# ProPrj_KiwiKey_2025-07-17.net
KiCad netlist of a schematic drawn in EasyEDA Pro
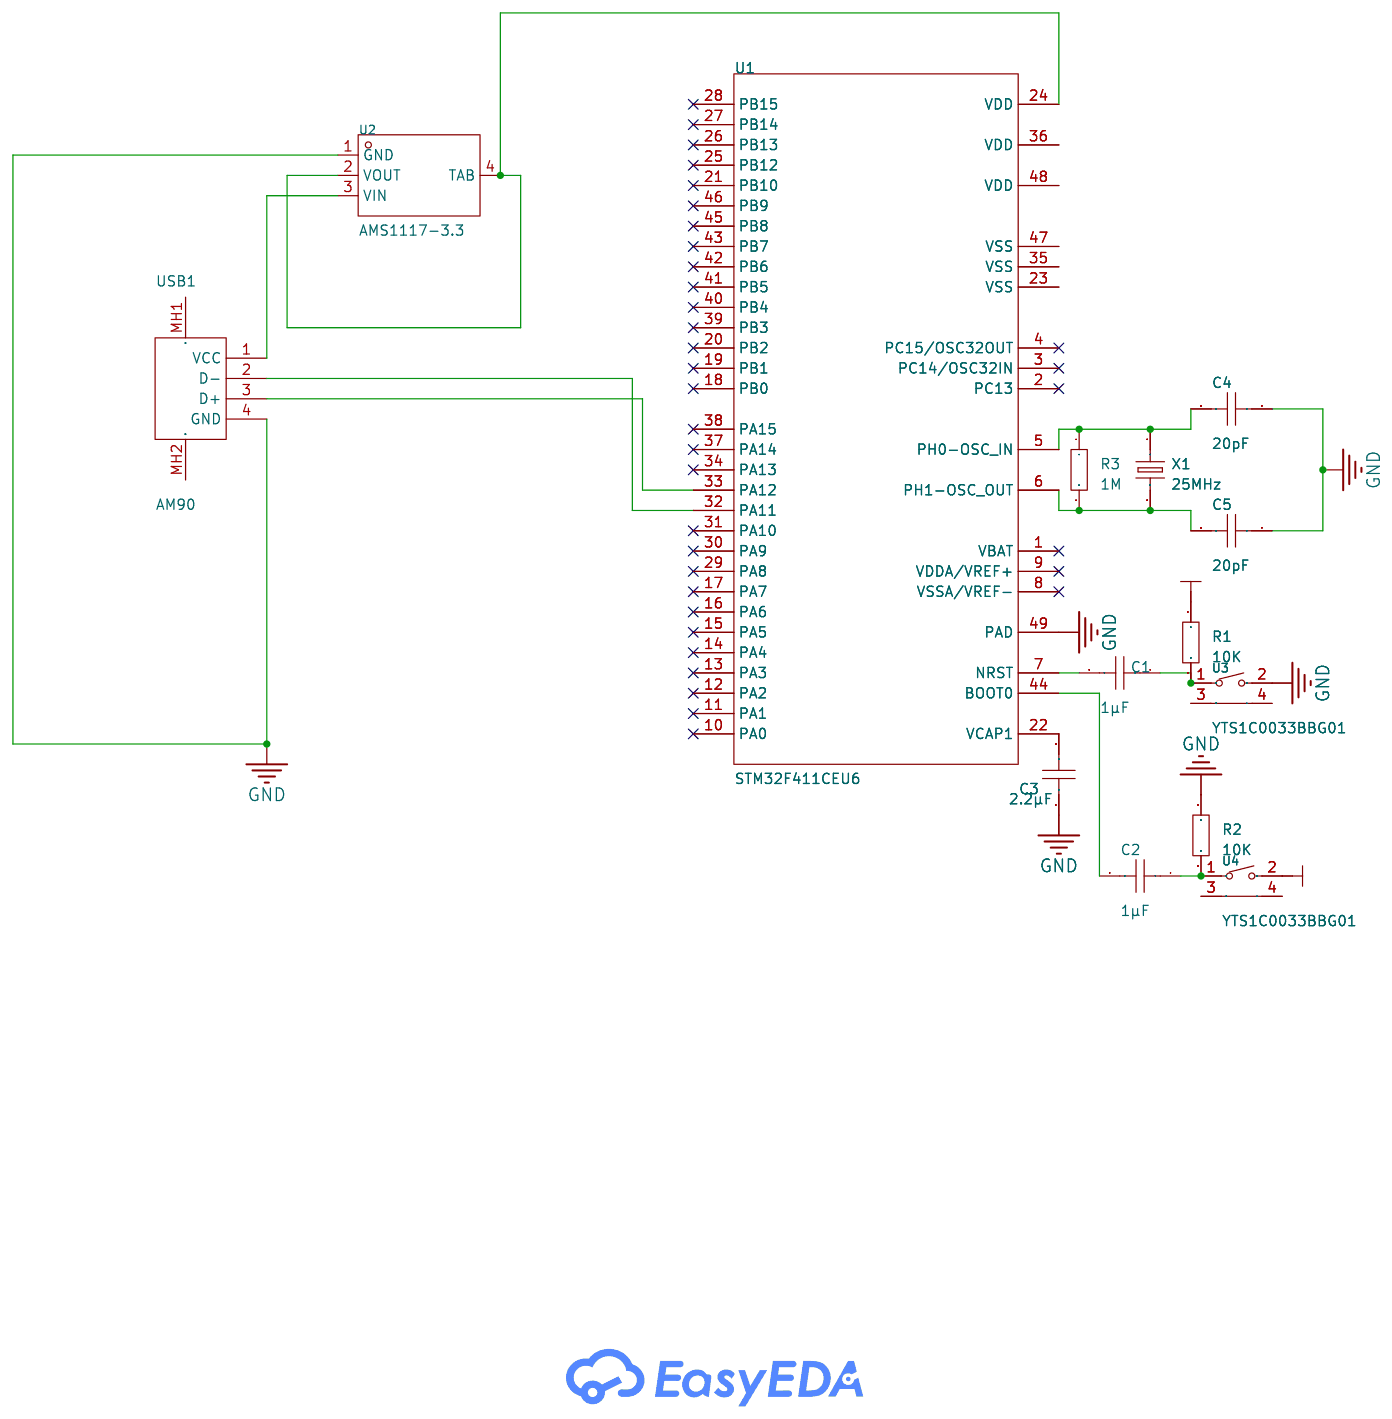
[diagram p0: schematic sheet]

(export (version "E")
  (design (tool "Eeschema 10.0.6"))
  (components
    (comp (ref "C1") (value "1µF") (footprint "easyedapro:C0603") (libsource (lib "easyedapro") (part "CAP")))
    (comp (ref "C2") (value "1µF") (footprint "easyedapro:C0603") (libsource (lib "easyedapro") (part "CAP")))
    (comp (ref "C3")
      (value "2.2µF")
      (footprint "easyedapro:C0603")
      (libsource (lib "easyedapro") (part "CAP"))
    )
    (comp (ref "C4")
      (value "20pF")
      (footprint "easyedapro:C0603")
      (libsource (lib "easyedapro") (part "CAP"))
    )
    (comp (ref "C5")
      (value "20pF")
      (footprint "easyedapro:C0603")
      (libsource (lib "easyedapro") (part "CAP"))
    )
    (comp (ref "R1") (value "10K") (footprint "easyedapro:R0603") (libsource (lib "easyedapro") (part "Res")))
    (comp (ref "R2") (value "10K") (footprint "easyedapro:R0603") (libsource (lib "easyedapro") (part "Res")))
    (comp (ref "R3") (value "1M") (footprint "easyedapro:R0603") (libsource (lib "easyedapro") (part "Res")))
    (comp (ref "U1")
      (value "STM32F411CEU6")
      (footprint "easyedapro:UFQFPN-48_L7.0-W7.0-P0.50-BL-EP")
      (fields (field (name "Manufacturer") "ST(意法半导体)"))
      (libsource (lib "easyedapro") (part "STM32F411CEU6"))
    )
    (comp (ref "U2")
      (value "AMS1117-3.3")
      (footprint "easyedapro:SOT-223-3_L6.5-W3.4-P2.30-LS7.0-BR")
      (fields (field (name "Manufacturer") "PUOLOP(迪浦)"))
      (libsource (lib "easyedapro") (part "AMS1117-3.3_C351784"))
    )
    (comp (ref "U3")
      (value "YTS1C0033BBG01")
      (footprint "easyedapro:SW-SMD_YIYUAN_YTS1C003XXX")
      (fields (field (name "Manufacturer") "YIYUAN(怡远)"))
      (libsource (lib "easyedapro") (part "YTS1C0033BBG01"))
    )
    (comp (ref "U4")
      (value "YTS1C0033BBG01")
      (footprint "easyedapro:SW-SMD_YIYUAN_YTS1C003XXX")
      (fields (field (name "Manufacturer") "YIYUAN(怡远)"))
      (libsource (lib "easyedapro") (part "YTS1C0033BBG01"))
    )
    (comp (ref "USB1")
      (value "AM90")
      (footprint "easyedapro:USB-AM-TH_AM90")
      (fields (field (name "Manufacturer") "SHOU HAN(首韩)"))
      (libsource (lib "easyedapro") (part "AM90"))
    )
    (comp (ref "X1")
      (value "25MHz")
      (footprint "easyedapro:HC-49US_L11.5-W4.5-P4.88")
      (fields
        (field (name "Manufacturer Part") "XIHCELNANF-25MHZ")
        (field (name "Manufacturer") "TAITIEN(泰艺电子)")
      )
      (libsource (lib "easyedapro") (part "XIHCELNANF-25MHZ"))
    )
  )
  (nets
    (net (code "1") (name "3.3V") (class "Default")
      (node (ref "R1") (pin "1") (pinfunction "1_1") (pintype "input"))
      (node (ref "U4") (pin "2") (pinfunction "2_2") (pintype "input"))
    )
    (net (code "2") (name "GND") (class "Default")
      (node (ref "C3") (pin "1") (pinfunction "1_1") (pintype "input"))
      (node (ref "C4") (pin "1") (pinfunction "1_1") (pintype "input"))
      (node (ref "C5") (pin "1") (pinfunction "1_1") (pintype "input"))
      (node (ref "R2") (pin "1") (pinfunction "1_1") (pintype "input"))
      (node (ref "U1") (pin "49") (pinfunction "PAD_49") (pintype "unspecified"))
      (node (ref "U2") (pin "1") (pinfunction "GND_1") (pintype "input"))
      (node (ref "U3") (pin "2") (pinfunction "2_2") (pintype "input"))
      (node (ref "USB1") (pin "4") (pinfunction "GND_4") (pintype "input"))
    )
    (net (code "3") (name "Net-(C1-Pad1)") (class "Default")
      (node (ref "C1") (pin "1") (pinfunction "1_1") (pintype "input"))
      (node (ref "R1") (pin "2") (pinfunction "2_2") (pintype "input"))
      (node (ref "U3") (pin "1") (pinfunction "1_1") (pintype "input"))
    )
    (net (code "4") (name "Net-(C2-Pad1)") (class "Default")
      (node (ref "C2") (pin "1") (pinfunction "1_1") (pintype "input"))
      (node (ref "R2") (pin "2") (pinfunction "2_2") (pintype "input"))
      (node (ref "U4") (pin "1") (pinfunction "1_1") (pintype "input"))
    )
    (net (code "5") (name "Net-(U1-BOOT0)") (class "Default")
      (node (ref "C2") (pin "2") (pinfunction "2_2") (pintype "input"))
      (node (ref "U1") (pin "44") (pinfunction "BOOT0_44") (pintype "input"))
    )
    (net (code "6") (name "Net-(U1-NRST)") (class "Default")
      (node (ref "C1") (pin "2") (pinfunction "2_2") (pintype "input"))
      (node (ref "U1") (pin "7") (pinfunction "NRST_7") (pintype "unspecified"))
    )
    (net (code "7") (name "Net-(U1-PA11)") (class "Default")
      (node (ref "U1") (pin "32") (pinfunction "PA11_32") (pintype "unspecified"))
      (node (ref "USB1") (pin "2") (pinfunction "D-_2") (pintype "input"))
    )
    (net (code "8") (name "Net-(U1-PA12)") (class "Default")
      (node (ref "U1") (pin "33") (pinfunction "PA12_33") (pintype "unspecified"))
      (node (ref "USB1") (pin "3") (pinfunction "D+_3") (pintype "input"))
    )
    (net (code "9") (name "Net-(U1-PH0-OSC_IN)") (class "Default")
      (node (ref "C4") (pin "2") (pinfunction "2_2") (pintype "input"))
      (node (ref "R3") (pin "1") (pinfunction "1_1") (pintype "input"))
      (node (ref "U1") (pin "5") (pinfunction "PH0-OSC_IN_5") (pintype "unspecified"))
      (node (ref "X1") (pin "1") (pinfunction "1_1") (pintype "unspecified"))
    )
    (net (code "10") (name "Net-(U1-PH1-OSC_OUT)") (class "Default")
      (node (ref "C5") (pin "2") (pinfunction "2_2") (pintype "input"))
      (node (ref "R3") (pin "2") (pinfunction "2_2") (pintype "input"))
      (node (ref "U1") (pin "6") (pinfunction "PH1-OSC_OUT_6") (pintype "unspecified"))
      (node (ref "X1") (pin "2") (pinfunction "2_2") (pintype "unspecified"))
    )
    (net (code "11") (name "Net-(U1-VCAP1)") (class "Default")
      (node (ref "C3") (pin "2") (pinfunction "2_2") (pintype "input"))
      (node (ref "U1") (pin "22") (pinfunction "VCAP1_22") (pintype "unspecified"))
    )
    (net (code "12") (name "Net-(U2-TAB)") (class "Default")
      (node (ref "U1") (pin "24") (pinfunction "VDD_24") (pintype "unspecified"))
      (node (ref "U2") (pin "2") (pinfunction "VOUT_2") (pintype "input"))
      (node (ref "U2") (pin "4") (pinfunction "TAB_4") (pintype "input"))
    )
    (net (code "13") (name "Net-(U2-VIN)") (class "Default")
      (node (ref "U2") (pin "3") (pinfunction "VIN_3") (pintype "input"))
      (node (ref "USB1") (pin "1") (pinfunction "VCC_1") (pintype "input"))
    )
    (net (code "14") (name "unconnected-(U1-PA0-Pad10)") (class "Default")
      (node (ref "U1") (pin "10") (pinfunction "PA0_10") (pintype "unspecified+no_connect"))
    )
    (net (code "15") (name "unconnected-(U1-PA1-Pad11)") (class "Default")
      (node (ref "U1") (pin "11") (pinfunction "PA1_11") (pintype "unspecified+no_connect"))
    )
    (net (code "16") (name "unconnected-(U1-PA2-Pad12)") (class "Default")
      (node (ref "U1") (pin "12") (pinfunction "PA2_12") (pintype "unspecified+no_connect"))
    )
    (net (code "17") (name "unconnected-(U1-PA3-Pad13)") (class "Default")
      (node (ref "U1") (pin "13") (pinfunction "PA3_13") (pintype "unspecified+no_connect"))
    )
    (net (code "18") (name "unconnected-(U1-PA4-Pad14)") (class "Default")
      (node (ref "U1") (pin "14") (pinfunction "PA4_14") (pintype "unspecified+no_connect"))
    )
    (net (code "19") (name "unconnected-(U1-PA5-Pad15)") (class "Default")
      (node (ref "U1") (pin "15") (pinfunction "PA5_15") (pintype "unspecified+no_connect"))
    )
    (net (code "20") (name "unconnected-(U1-PA6-Pad16)") (class "Default")
      (node (ref "U1") (pin "16") (pinfunction "PA6_16") (pintype "unspecified+no_connect"))
    )
    (net (code "21") (name "unconnected-(U1-PA7-Pad17)") (class "Default")
      (node (ref "U1") (pin "17") (pinfunction "PA7_17") (pintype "unspecified+no_connect"))
    )
    (net (code "22") (name "unconnected-(U1-PA8-Pad29)") (class "Default")
      (node (ref "U1") (pin "29") (pinfunction "PA8_29") (pintype "unspecified+no_connect"))
    )
    (net (code "23") (name "unconnected-(U1-PA9-Pad30)") (class "Default")
      (node (ref "U1") (pin "30") (pinfunction "PA9_30") (pintype "unspecified+no_connect"))
    )
    (net (code "24") (name "unconnected-(U1-PA10-Pad31)") (class "Default")
      (node (ref "U1") (pin "31") (pinfunction "PA10_31") (pintype "unspecified+no_connect"))
    )
    (net (code "25") (name "unconnected-(U1-PA13-Pad34)") (class "Default")
      (node (ref "U1") (pin "34") (pinfunction "PA13_34") (pintype "unspecified+no_connect"))
    )
    (net (code "26") (name "unconnected-(U1-PA14-Pad37)") (class "Default")
      (node (ref "U1") (pin "37") (pinfunction "PA14_37") (pintype "unspecified+no_connect"))
    )
    (net (code "27") (name "unconnected-(U1-PA15-Pad38)") (class "Default")
      (node (ref "U1") (pin "38") (pinfunction "PA15_38") (pintype "unspecified+no_connect"))
    )
    (net (code "28") (name "unconnected-(U1-PB0-Pad18)") (class "Default")
      (node (ref "U1") (pin "18") (pinfunction "PB0_18") (pintype "unspecified+no_connect"))
    )
    (net (code "29") (name "unconnected-(U1-PB1-Pad19)") (class "Default")
      (node (ref "U1") (pin "19") (pinfunction "PB1_19") (pintype "unspecified+no_connect"))
    )
    (net (code "30") (name "unconnected-(U1-PB2-Pad20)") (class "Default")
      (node (ref "U1") (pin "20") (pinfunction "PB2_20") (pintype "unspecified+no_connect"))
    )
    (net (code "31") (name "unconnected-(U1-PB3-Pad39)") (class "Default")
      (node (ref "U1") (pin "39") (pinfunction "PB3_39") (pintype "unspecified+no_connect"))
    )
    (net (code "32") (name "unconnected-(U1-PB4-Pad40)") (class "Default")
      (node (ref "U1") (pin "40") (pinfunction "PB4_40") (pintype "unspecified+no_connect"))
    )
    (net (code "33") (name "unconnected-(U1-PB5-Pad41)") (class "Default")
      (node (ref "U1") (pin "41") (pinfunction "PB5_41") (pintype "unspecified+no_connect"))
    )
    (net (code "34") (name "unconnected-(U1-PB6-Pad42)") (class "Default")
      (node (ref "U1") (pin "42") (pinfunction "PB6_42") (pintype "unspecified+no_connect"))
    )
    (net (code "35") (name "unconnected-(U1-PB7-Pad43)") (class "Default")
      (node (ref "U1") (pin "43") (pinfunction "PB7_43") (pintype "unspecified+no_connect"))
    )
    (net (code "36") (name "unconnected-(U1-PB8-Pad45)") (class "Default")
      (node (ref "U1") (pin "45") (pinfunction "PB8_45") (pintype "unspecified+no_connect"))
    )
    (net (code "37") (name "unconnected-(U1-PB9-Pad46)") (class "Default")
      (node (ref "U1") (pin "46") (pinfunction "PB9_46") (pintype "unspecified+no_connect"))
    )
    (net (code "38") (name "unconnected-(U1-PB10-Pad21)") (class "Default")
      (node (ref "U1") (pin "21") (pinfunction "PB10_21") (pintype "unspecified+no_connect"))
    )
    (net (code "39") (name "unconnected-(U1-PB12-Pad25)") (class "Default")
      (node (ref "U1") (pin "25") (pinfunction "PB12_25") (pintype "unspecified+no_connect"))
    )
    (net (code "40") (name "unconnected-(U1-PB13-Pad26)") (class "Default")
      (node (ref "U1") (pin "26") (pinfunction "PB13_26") (pintype "unspecified+no_connect"))
    )
    (net (code "41") (name "unconnected-(U1-PB14-Pad27)") (class "Default")
      (node (ref "U1") (pin "27") (pinfunction "PB14_27") (pintype "unspecified+no_connect"))
    )
    (net (code "42") (name "unconnected-(U1-PB15-Pad28)") (class "Default")
      (node (ref "U1") (pin "28") (pinfunction "PB15_28") (pintype "unspecified+no_connect"))
    )
    (net (code "43") (name "unconnected-(U1-PC13-Pad2)") (class "Default")
      (node (ref "U1") (pin "2") (pinfunction "PC13_2") (pintype "unspecified+no_connect"))
    )
    (net (code "44") (name "unconnected-(U1-PC14{slash}OSC32IN-Pad3)") (class "Default")
      (node (ref "U1") (pin "3") (pinfunction "PC14/OSC32IN_3") (pintype "unspecified+no_connect"))
    )
    (net (code "45") (name "unconnected-(U1-PC15{slash}OSC32OUT-Pad4)") (class "Default")
      (node (ref "U1") (pin "4") (pinfunction "PC15/OSC32OUT_4") (pintype "unspecified+no_connect"))
    )
    (net (code "46") (name "unconnected-(U1-VBAT-Pad1)") (class "Default")
      (node (ref "U1") (pin "1") (pinfunction "VBAT_1") (pintype "unspecified+no_connect"))
    )
    (net (code "47") (name "unconnected-(U1-VDD-Pad36)") (class "Default")
      (node (ref "U1") (pin "36") (pinfunction "VDD_36") (pintype "unspecified"))
    )
    (net (code "48") (name "unconnected-(U1-VDD-Pad48)") (class "Default")
      (node (ref "U1") (pin "48") (pinfunction "VDD_48") (pintype "unspecified"))
    )
    (net (code "49") (name "unconnected-(U1-VDDA{slash}VREF+-Pad9)") (class "Default")
      (node (ref "U1") (pin "9") (pinfunction "VDDA/VREF+_9") (pintype "unspecified+no_connect"))
    )
    (net (code "50") (name "unconnected-(U1-VSS-Pad23)") (class "Default")
      (node (ref "U1") (pin "23") (pinfunction "VSS_23") (pintype "unspecified"))
    )
    (net (code "51") (name "unconnected-(U1-VSS-Pad35)") (class "Default")
      (node (ref "U1") (pin "35") (pinfunction "VSS_35") (pintype "unspecified"))
    )
    (net (code "52") (name "unconnected-(U1-VSS-Pad47)") (class "Default")
      (node (ref "U1") (pin "47") (pinfunction "VSS_47") (pintype "unspecified"))
    )
    (net (code "53") (name "unconnected-(U1-VSSA{slash}VREF--Pad8)") (class "Default")
      (node (ref "U1") (pin "8") (pinfunction "VSSA/VREF-_8") (pintype "unspecified+no_connect"))
    )
    (net (code "54") (name "unconnected-(U3-Pad3)") (class "Default")
      (node (ref "U3") (pin "3") (pinfunction "3_3") (pintype "input"))
    )
    (net (code "55") (name "unconnected-(U3-Pad4)") (class "Default")
      (node (ref "U3") (pin "4") (pinfunction "4_4") (pintype "input"))
    )
    (net (code "56") (name "unconnected-(U4-Pad3)") (class "Default")
      (node (ref "U4") (pin "3") (pinfunction "3_3") (pintype "input"))
    )
    (net (code "57") (name "unconnected-(U4-Pad4)") (class "Default")
      (node (ref "U4") (pin "4") (pinfunction "4_4") (pintype "input"))
    )
    (net (code "58") (name "unconnected-(USB1-PadMH1)") (class "Default")
      (node (ref "USB1") (pin "MH1") (pinfunction "MH1_MH1") (pintype "unspecified"))
    )
    (net (code "59") (name "unconnected-(USB1-PadMH2)") (class "Default")
      (node (ref "USB1") (pin "MH2") (pinfunction "MH2_MH2") (pintype "unspecified"))
    )
  )
)
